# FunctionalGeneratorPCBGhebeh.net
KiCad netlist of a schematic drawn in EAGLE
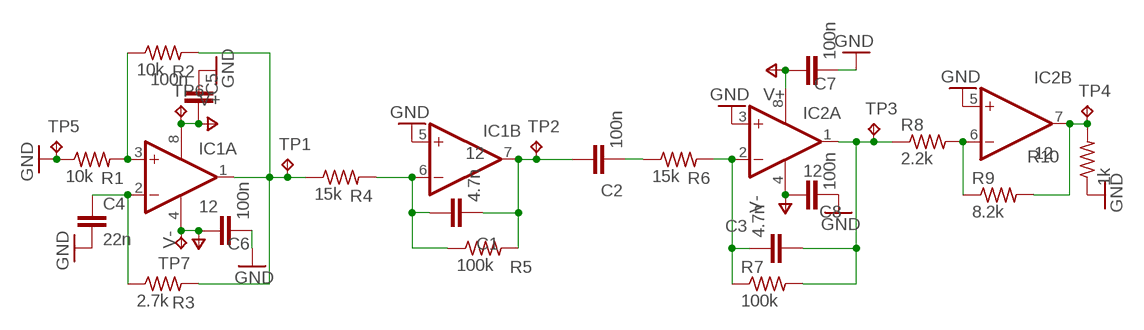
[diagram p0: schematic, sheet 1]

(export (version "E")
  (design (tool "Eeschema 10.0.6"))
  (components
    (comp (ref "C1")
      (value "4.7n")
      (footprint "eagle-import:C5B3")
      (libsource (lib "eagle-import") (part "C5/3"))
    )
    (comp (ref "C2")
      (value "100n")
      (footprint "eagle-import:C5B3")
      (libsource (lib "eagle-import") (part "C5/3"))
    )
    (comp (ref "C3")
      (value "4.7n")
      (footprint "eagle-import:C5B3")
      (libsource (lib "eagle-import") (part "C5/3"))
    )
    (comp (ref "C4")
      (value "22n")
      (footprint "eagle-import:C5B3")
      (libsource (lib "eagle-import") (part "C5/3"))
    )
    (comp (ref "C5")
      (value "100n")
      (footprint "eagle-import:C5B3")
      (libsource (lib "eagle-import") (part "C5/3"))
    )
    (comp (ref "C6")
      (value "100n")
      (footprint "eagle-import:C5B3")
      (libsource (lib "eagle-import") (part "C5/3"))
    )
    (comp (ref "C7")
      (value "100n")
      (footprint "eagle-import:C5B3")
      (libsource (lib "eagle-import") (part "C5/3"))
    )
    (comp (ref "C8")
      (value "100n")
      (footprint "eagle-import:C5B3")
      (libsource (lib "eagle-import") (part "C5/3"))
    )
    (comp (ref "IC1")
      (value "12")
      (footprint "eagle-import:DIL08")
      (libsource (lib "eagle-import") (part "OPA2P"))
    )
    (comp (ref "IC2")
      (value "12")
      (footprint "eagle-import:DIL08")
      (libsource (lib "eagle-import") (part "OPA2P"))
    )
    (comp (ref "R1")
      (value "10k")
      (footprint "eagle-import:0309_10")
      (libsource (lib "eagle-import") (part "R-US_0309/10"))
    )
    (comp (ref "R2")
      (value "10k")
      (footprint "eagle-import:0309_10")
      (libsource (lib "eagle-import") (part "R-US_0309/10"))
    )
    (comp (ref "R3")
      (value "2.7k")
      (footprint "eagle-import:0309_10")
      (libsource (lib "eagle-import") (part "R-US_0309/10"))
    )
    (comp (ref "R4")
      (value "15k")
      (footprint "eagle-import:0309_10")
      (libsource (lib "eagle-import") (part "R-US_0309/10"))
    )
    (comp (ref "R5")
      (value "100k")
      (footprint "eagle-import:0309_10")
      (libsource (lib "eagle-import") (part "R-US_0309/10"))
    )
    (comp (ref "R6")
      (value "15k")
      (footprint "eagle-import:0309_10")
      (libsource (lib "eagle-import") (part "R-US_0309/10"))
    )
    (comp (ref "R7")
      (value "100k")
      (footprint "eagle-import:0309_10")
      (libsource (lib "eagle-import") (part "R-US_0309/10"))
    )
    (comp (ref "R8")
      (value "2.2k")
      (footprint "eagle-import:0309_10")
      (libsource (lib "eagle-import") (part "R-US_0309/10"))
    )
    (comp (ref "R9")
      (value "8.2k")
      (footprint "eagle-import:0309_10")
      (libsource (lib "eagle-import") (part "R-US_0309/10"))
    )
    (comp (ref "R10")
      (value "1k")
      (footprint "eagle-import:0309_10")
      (libsource (lib "eagle-import") (part "R-US_0309/10"))
    )
    (comp (ref "TP1")
      (value "TPPAD1-13Y")
      (footprint "eagle-import:P1-13Y")
      (libsource (lib "eagle-import") (part "TPPAD1-13Y"))
    )
    (comp (ref "TP2")
      (value "TPPAD1-13Y")
      (footprint "eagle-import:P1-13Y")
      (libsource (lib "eagle-import") (part "TPPAD1-13Y"))
    )
    (comp (ref "TP3")
      (value "TPPAD1-13Y")
      (footprint "eagle-import:P1-13Y")
      (libsource (lib "eagle-import") (part "TPPAD1-13Y"))
    )
    (comp (ref "TP4")
      (value "TPPAD1-13Y")
      (footprint "eagle-import:P1-13Y")
      (libsource (lib "eagle-import") (part "TPPAD1-13Y"))
    )
    (comp (ref "TP5")
      (value "TPPAD1-13Y")
      (footprint "eagle-import:P1-13Y")
      (libsource (lib "eagle-import") (part "TPPAD1-13Y"))
    )
    (comp (ref "TP6")
      (value "TPPAD1-13Y")
      (footprint "eagle-import:P1-13Y")
      (libsource (lib "eagle-import") (part "TPPAD1-13Y"))
    )
    (comp (ref "TP7")
      (value "TPPAD1-13Y")
      (footprint "eagle-import:P1-13Y")
      (libsource (lib "eagle-import") (part "TPPAD1-13Y"))
    )
  )
  (nets
    (net (code "1") (name "GND") (class "Default")
      (node (ref "C4") (pin "2") (pinfunction "2_2") (pintype "passive"))
      (node (ref "C5") (pin "2") (pinfunction "2_2") (pintype "passive"))
      (node (ref "C6") (pin "2") (pinfunction "2_2") (pintype "passive"))
      (node (ref "C7") (pin "2") (pinfunction "2_2") (pintype "passive"))
      (node (ref "C8") (pin "1") (pinfunction "1_1") (pintype "passive"))
      (node (ref "IC1") (pin "5") (pinfunction "+IN_5") (pintype "input"))
      (node (ref "IC2") (pin "3") (pinfunction "+IN_3") (pintype "input"))
      (node (ref "IC2") (pin "5") (pinfunction "+IN_5") (pintype "input"))
      (node (ref "R1") (pin "1") (pinfunction "1_1") (pintype "passive"))
      (node (ref "R10") (pin "1") (pinfunction "1_1") (pintype "passive"))
      (node (ref "TP5") (pin "TP") (pinfunction "TP_TP") (pintype "input"))
    )
    (net (code "2") (name "Net-(C2-Pad2)") (class "Default")
      (node (ref "C2") (pin "2") (pinfunction "2_2") (pintype "passive"))
      (node (ref "R6") (pin "1") (pinfunction "1_1") (pintype "passive"))
    )
    (net (code "3") (name "Net-(IC1A-+IN)") (class "Default")
      (node (ref "IC1") (pin "3") (pinfunction "+IN_3") (pintype "input"))
      (node (ref "R1") (pin "2") (pinfunction "2_2") (pintype "passive"))
      (node (ref "R2") (pin "1") (pinfunction "1_1") (pintype "passive"))
    )
    (net (code "4") (name "Net-(IC1A--IN)") (class "Default")
      (node (ref "C4") (pin "1") (pinfunction "1_1") (pintype "passive"))
      (node (ref "IC1") (pin "2") (pinfunction "-IN_2") (pintype "input"))
      (node (ref "R3") (pin "1") (pinfunction "1_1") (pintype "passive"))
    )
    (net (code "5") (name "Net-(IC1A-OUT)") (class "Default")
      (node (ref "IC1") (pin "1") (pinfunction "OUT_1") (pintype "output"))
      (node (ref "R2") (pin "2") (pinfunction "2_2") (pintype "passive"))
      (node (ref "R3") (pin "2") (pinfunction "2_2") (pintype "passive"))
      (node (ref "R4") (pin "1") (pinfunction "1_1") (pintype "passive"))
      (node (ref "TP1") (pin "TP") (pinfunction "TP_TP") (pintype "input"))
    )
    (net (code "6") (name "Net-(IC1B--IN)") (class "Default")
      (node (ref "C1") (pin "1") (pinfunction "1_1") (pintype "passive"))
      (node (ref "IC1") (pin "6") (pinfunction "-IN_6") (pintype "input"))
      (node (ref "R4") (pin "2") (pinfunction "2_2") (pintype "passive"))
      (node (ref "R5") (pin "1") (pinfunction "1_1") (pintype "passive"))
    )
    (net (code "7") (name "Net-(IC1B-OUT)") (class "Default")
      (node (ref "C1") (pin "2") (pinfunction "2_2") (pintype "passive"))
      (node (ref "C2") (pin "1") (pinfunction "1_1") (pintype "passive"))
      (node (ref "IC1") (pin "7") (pinfunction "OUT_7") (pintype "output"))
      (node (ref "R5") (pin "2") (pinfunction "2_2") (pintype "passive"))
      (node (ref "TP2") (pin "TP") (pinfunction "TP_TP") (pintype "input"))
    )
    (net (code "8") (name "Net-(IC2A--IN)") (class "Default")
      (node (ref "C3") (pin "1") (pinfunction "1_1") (pintype "passive"))
      (node (ref "IC2") (pin "2") (pinfunction "-IN_2") (pintype "input"))
      (node (ref "R6") (pin "2") (pinfunction "2_2") (pintype "passive"))
      (node (ref "R7") (pin "1") (pinfunction "1_1") (pintype "passive"))
    )
    (net (code "9") (name "Net-(IC2A-OUT)") (class "Default")
      (node (ref "C3") (pin "2") (pinfunction "2_2") (pintype "passive"))
      (node (ref "IC2") (pin "1") (pinfunction "OUT_1") (pintype "output"))
      (node (ref "R7") (pin "2") (pinfunction "2_2") (pintype "passive"))
      (node (ref "R8") (pin "1") (pinfunction "1_1") (pintype "passive"))
      (node (ref "TP3") (pin "TP") (pinfunction "TP_TP") (pintype "input"))
    )
    (net (code "10") (name "Net-(IC2B--IN)") (class "Default")
      (node (ref "IC2") (pin "6") (pinfunction "-IN_6") (pintype "input"))
      (node (ref "R8") (pin "2") (pinfunction "2_2") (pintype "passive"))
      (node (ref "R9") (pin "1") (pinfunction "1_1") (pintype "passive"))
    )
    (net (code "11") (name "Net-(IC2B-OUT)") (class "Default")
      (node (ref "IC2") (pin "7") (pinfunction "OUT_7") (pintype "output"))
      (node (ref "R10") (pin "2") (pinfunction "2_2") (pintype "passive"))
      (node (ref "R9") (pin "2") (pinfunction "2_2") (pintype "passive"))
      (node (ref "TP4") (pin "TP") (pinfunction "TP_TP") (pintype "input"))
    )
    (net (code "12") (name "V+") (class "Default")
      (node (ref "C5") (pin "1") (pinfunction "1_1") (pintype "passive"))
      (node (ref "C7") (pin "1") (pinfunction "1_1") (pintype "passive"))
      (node (ref "IC1") (pin "8") (pinfunction "V+_8") (pintype "power_in"))
      (node (ref "IC2") (pin "8") (pinfunction "V+_8") (pintype "power_in"))
      (node (ref "TP6") (pin "TP") (pinfunction "TP_TP") (pintype "input"))
    )
    (net (code "13") (name "V-") (class "Default")
      (node (ref "C6") (pin "1") (pinfunction "1_1") (pintype "passive"))
      (node (ref "C8") (pin "2") (pinfunction "2_2") (pintype "passive"))
      (node (ref "IC1") (pin "4") (pinfunction "V-_4") (pintype "power_in"))
      (node (ref "IC2") (pin "4") (pinfunction "V-_4") (pintype "power_in"))
      (node (ref "TP7") (pin "TP") (pinfunction "TP_TP") (pintype "input"))
    )
  )
)
